# TFT.net
KiCad netlist of a schematic drawn in Altium Designer
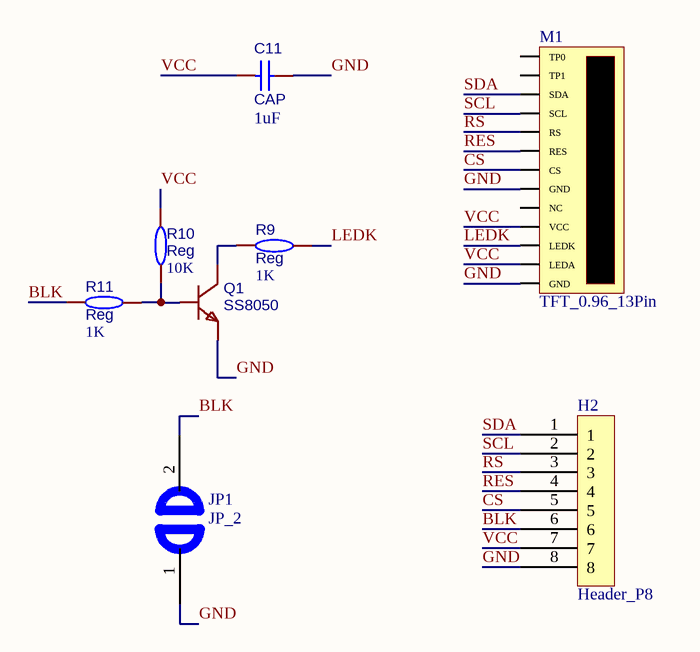
[diagram p0: TFT.SchDoc]

(export (version "E")
  (design (tool "Eeschema 10.0.6"))
  (components
    (comp (ref "C11")
      (value "CAP")
      (footprint "C0603")
      (description "Cap")
      (fields
        (field (name "BOM_SUPPLIER PART") "C302008")
        (field (name "BOM_MANUFACTURER PART") "0603B103K101CT")
        (field (name "ALTIUM_VALUE") "1uF")
        (field (name "CONTRIBUTOR") "LCSC")
      )
      (libsource (lib "Levent_lib") (part "CAP"))
    )
    (comp (ref "H2")
      (value "Header_P8")
      (footprint "H_2.54_P8")
      (description "8Pin排针")
      (libsource (lib "Levent_lib") (part "Header_P8"))
    )
    (comp (ref "JP1")
      (value "JP_2")
      (footprint "JP_2Pin")
      (description "2Pin跳线焊盘")
      (libsource (lib "Levent_lib") (part "JP_2"))
    )
    (comp (ref "M1")
      (value "TFT_0.96_13Pin")
      (footprint "TFT_0.96_13Pin")
      (description "ST7735_TFT")
      (libsource (lib "Levent_lib") (part "TFT_0.96_13Pin"))
    )
    (comp (ref "Q1")
      (value "SS8050")
      (footprint "SOT-23-3")
      (description "NPN")
      (fields (field (name "BOM_SUPPLIER PART") "C541705") (field (name "CONTRIBUTOR") "LCSC"))
      (libsource (lib "Levent_lib") (part "SS8050"))
    )
    (comp (ref "R9")
      (value "Reg")
      (footprint "R0603")
      (description "电阻")
      (fields
        (field (name "BOM_SUPPLIER PART") "C465721")
        (field (name "BOM_MANUFACTURER PART") "AR03BTCX1002A")
        (field (name "ALTIUM_VALUE") "1K")
        (field (name "CONTRIBUTOR") "LCSC")
      )
      (libsource (lib "Levent_lib") (part "Res"))
    )
    (comp (ref "R10")
      (value "Reg")
      (footprint "R0603")
      (description "电阻")
      (fields
        (field (name "BOM_SUPPLIER PART") "C465721")
        (field (name "BOM_MANUFACTURER PART") "AR03BTCX1002A")
        (field (name "ALTIUM_VALUE") "10K")
        (field (name "CONTRIBUTOR") "LCSC")
      )
      (libsource (lib "Levent_lib") (part "Res"))
    )
    (comp (ref "R11")
      (value "Reg")
      (footprint "R0603")
      (description "电阻")
      (fields
        (field (name "BOM_SUPPLIER PART") "C465721")
        (field (name "BOM_MANUFACTURER PART") "AR03BTCX1002A")
        (field (name "ALTIUM_VALUE") "1K")
        (field (name "CONTRIBUTOR") "LCSC")
      )
      (libsource (lib "Levent_lib") (part "Res"))
    )
  )
  (nets
    (net (code "1") (name "/BLK") (class "Default")
      (node (ref "H2") (pin "6") (pinfunction "6_6") (pintype "passive"))
      (node (ref "JP1") (pin "2") (pinfunction "2_2") (pintype "passive"))
      (node (ref "R11") (pin "1") (pinfunction "1_1") (pintype "passive"))
    )
    (net (code "2") (name "/CS") (class "Default")
      (node (ref "H2") (pin "5") (pinfunction "5_5") (pintype "passive"))
      (node (ref "M1") (pin "7") (pinfunction "CS_7") (pintype "passive"))
    )
    (net (code "3") (name "/GND") (class "Default")
      (node (ref "C11") (pin "2") (pinfunction "2_2") (pintype "passive"))
      (node (ref "H2") (pin "8") (pinfunction "8_8") (pintype "passive"))
      (node (ref "JP1") (pin "1") (pinfunction "1_1") (pintype "passive"))
      (node (ref "M1") (pin "13") (pinfunction "GND_13") (pintype "passive"))
      (node (ref "M1") (pin "8") (pinfunction "GND_8") (pintype "passive"))
      (node (ref "Q1") (pin "2") (pinfunction "E_2") (pintype "passive"))
    )
    (net (code "4") (name "/LEDK") (class "Default")
      (node (ref "M1") (pin "11") (pinfunction "LEDK_11") (pintype "passive"))
      (node (ref "R9") (pin "2") (pinfunction "2_2") (pintype "passive"))
    )
    (net (code "5") (name "/RES") (class "Default")
      (node (ref "H2") (pin "4") (pinfunction "4_4") (pintype "passive"))
      (node (ref "M1") (pin "6") (pinfunction "RES_6") (pintype "passive"))
    )
    (net (code "6") (name "/RS") (class "Default")
      (node (ref "H2") (pin "3") (pinfunction "3_3") (pintype "passive"))
      (node (ref "M1") (pin "5") (pinfunction "RS_5") (pintype "passive"))
    )
    (net (code "7") (name "/SCL") (class "Default")
      (node (ref "H2") (pin "2") (pinfunction "2_2") (pintype "passive"))
      (node (ref "M1") (pin "4") (pinfunction "SCL_4") (pintype "passive"))
    )
    (net (code "8") (name "/SDA") (class "Default")
      (node (ref "H2") (pin "1") (pinfunction "1_1") (pintype "passive"))
      (node (ref "M1") (pin "3") (pinfunction "SDA_3") (pintype "passive"))
    )
    (net (code "9") (name "/VCC") (class "Default")
      (node (ref "C11") (pin "1") (pinfunction "1_1") (pintype "passive"))
      (node (ref "H2") (pin "7") (pinfunction "7_7") (pintype "passive"))
      (node (ref "M1") (pin "10") (pinfunction "VCC_10") (pintype "passive"))
      (node (ref "M1") (pin "12") (pinfunction "LEDA_12") (pintype "passive"))
      (node (ref "R10") (pin "2") (pinfunction "2_2") (pintype "passive"))
    )
    (net (code "10") (name "Net-(Q1-B)") (class "Default")
      (node (ref "Q1") (pin "1") (pinfunction "B_1") (pintype "passive"))
      (node (ref "R10") (pin "1") (pinfunction "1_1") (pintype "passive"))
      (node (ref "R11") (pin "2") (pinfunction "2_2") (pintype "passive"))
    )
    (net (code "11") (name "Net-(Q1-C)") (class "Default")
      (node (ref "Q1") (pin "3") (pinfunction "C_3") (pintype "passive"))
      (node (ref "R9") (pin "1") (pinfunction "1_1") (pintype "passive"))
    )
    (net (code "12") (name "unconnected-(M1-NC-Pad9)") (class "Default")
      (node (ref "M1") (pin "9") (pinfunction "NC_9") (pintype "passive"))
    )
    (net (code "13") (name "unconnected-(M1-TP0-Pad1)") (class "Default")
      (node (ref "M1") (pin "1") (pinfunction "TP0_1") (pintype "passive"))
    )
    (net (code "14") (name "unconnected-(M1-TP1-Pad2)") (class "Default")
      (node (ref "M1") (pin "2") (pinfunction "TP1_2") (pintype "passive"))
    )
  )
)
